# pcb2.net
KiCad netlist of a schematic drawn in EAGLE
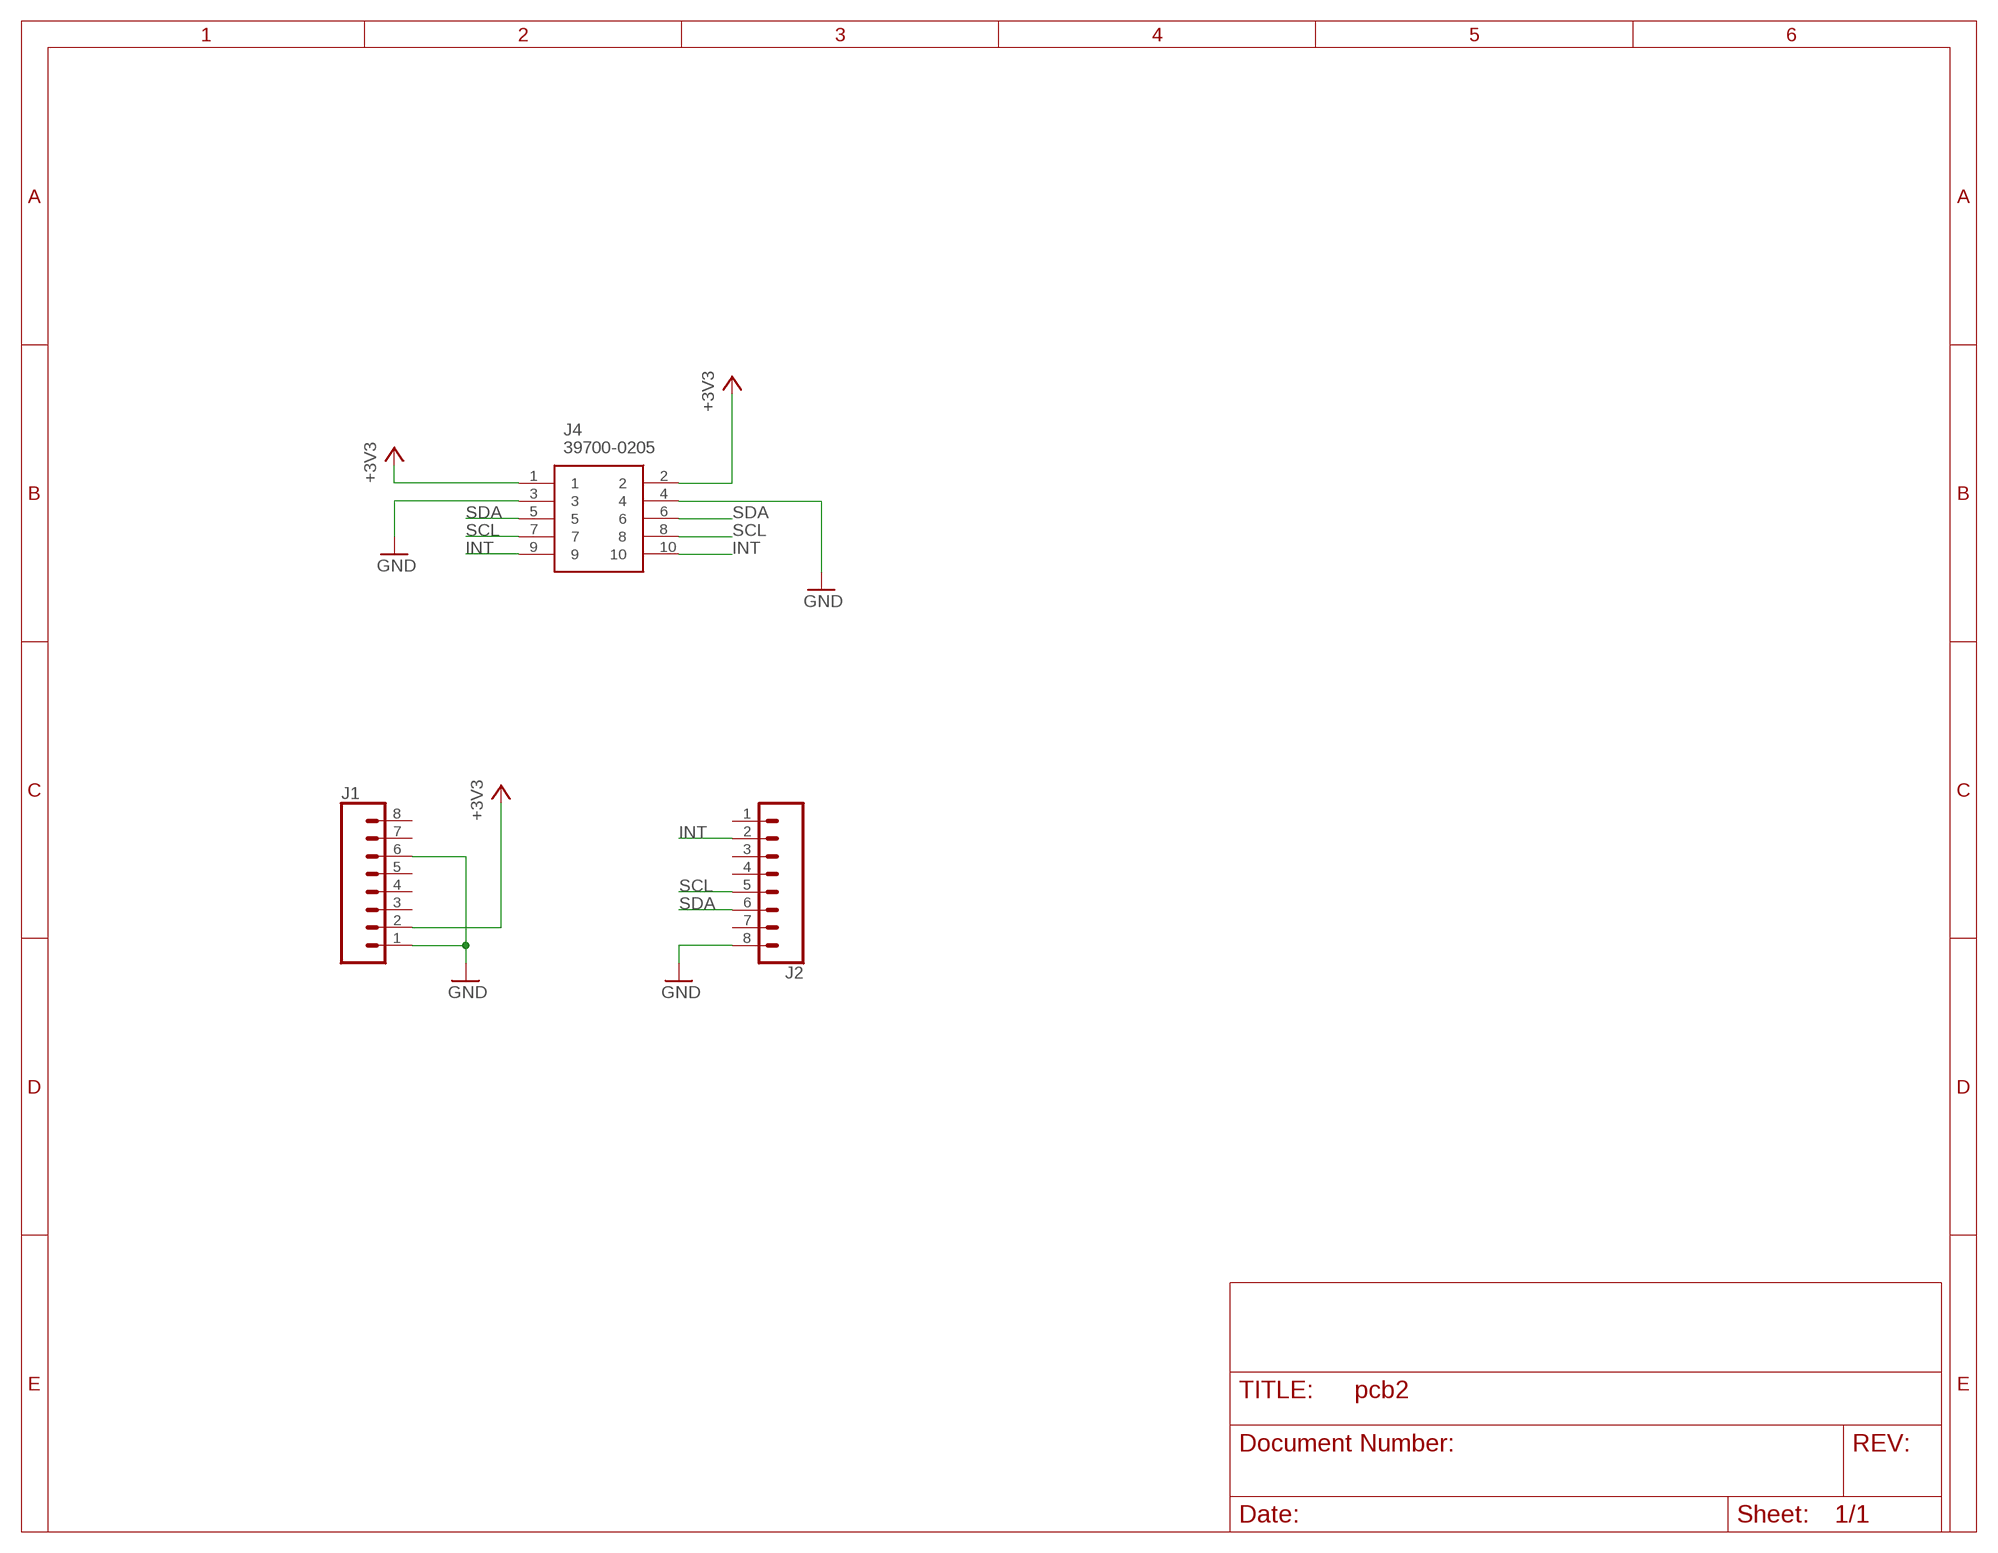
[diagram p0: schematic, sheet 1]

(export (version "E")
  (design (tool "Eeschema 10.0.6"))
  (components
    (comp (ref "J1")
      (value "CONN_08\"")
      (footprint "eagle-import:1X08")
      (libsource (lib "eagle-import") (part "CONN_08{dblquote}"))
    )
    (comp (ref "J2")
      (value "CONN_08\"")
      (footprint "eagle-import:1X08")
      (libsource (lib "eagle-import") (part "CONN_08{dblquote}"))
    )
    (comp (ref "J4")
      (value "39700-0205")
      (footprint "eagle-import:397000205")
      (fields (field (name "MOUSER_PART_NUMBER") "538-39700-0205"))
      (libsource (lib "eagle-import") (part "39700-0205"))
    )
  )
  (nets
    (net (code "1") (name "+3V3") (class "Default")
      (node (ref "J1") (pin "2") (pinfunction "2_2") (pintype "passive"))
      (node (ref "J4") (pin "1") (pinfunction "1_1") (pintype "bidirectional"))
      (node (ref "J4") (pin "2") (pinfunction "2_2") (pintype "bidirectional"))
    )
    (net (code "2") (name "/INT") (class "Default")
      (node (ref "J2") (pin "2") (pinfunction "2_2") (pintype "passive"))
      (node (ref "J4") (pin "10") (pinfunction "10_10") (pintype "bidirectional"))
      (node (ref "J4") (pin "9") (pinfunction "9_9") (pintype "bidirectional"))
    )
    (net (code "3") (name "/SCL") (class "Default")
      (node (ref "J2") (pin "5") (pinfunction "5_5") (pintype "passive"))
      (node (ref "J4") (pin "7") (pinfunction "7_7") (pintype "bidirectional"))
      (node (ref "J4") (pin "8") (pinfunction "8_8") (pintype "bidirectional"))
    )
    (net (code "4") (name "/SDA") (class "Default")
      (node (ref "J2") (pin "6") (pinfunction "6_6") (pintype "passive"))
      (node (ref "J4") (pin "5") (pinfunction "5_5") (pintype "bidirectional"))
      (node (ref "J4") (pin "6") (pinfunction "6_6") (pintype "bidirectional"))
    )
    (net (code "5") (name "GND") (class "Default")
      (node (ref "J1") (pin "1") (pinfunction "1_1") (pintype "passive"))
      (node (ref "J1") (pin "6") (pinfunction "6_6") (pintype "passive"))
      (node (ref "J2") (pin "8") (pinfunction "8_8") (pintype "passive"))
      (node (ref "J4") (pin "3") (pinfunction "3_3") (pintype "bidirectional"))
      (node (ref "J4") (pin "4") (pinfunction "4_4") (pintype "bidirectional"))
    )
    (net (code "6") (name "unconnected-(J1-Pad3)") (class "Default")
      (node (ref "J1") (pin "3") (pinfunction "3_3") (pintype "passive"))
    )
    (net (code "7") (name "unconnected-(J1-Pad4)") (class "Default")
      (node (ref "J1") (pin "4") (pinfunction "4_4") (pintype "passive"))
    )
    (net (code "8") (name "unconnected-(J1-Pad5)") (class "Default")
      (node (ref "J1") (pin "5") (pinfunction "5_5") (pintype "passive"))
    )
    (net (code "9") (name "unconnected-(J1-Pad7)") (class "Default")
      (node (ref "J1") (pin "7") (pinfunction "7_7") (pintype "passive"))
    )
    (net (code "10") (name "unconnected-(J1-Pad8)") (class "Default")
      (node (ref "J1") (pin "8") (pinfunction "8_8") (pintype "passive"))
    )
    (net (code "11") (name "unconnected-(J2-Pad1)") (class "Default")
      (node (ref "J2") (pin "1") (pinfunction "1_1") (pintype "passive"))
    )
    (net (code "12") (name "unconnected-(J2-Pad3)") (class "Default")
      (node (ref "J2") (pin "3") (pinfunction "3_3") (pintype "passive"))
    )
    (net (code "13") (name "unconnected-(J2-Pad4)") (class "Default")
      (node (ref "J2") (pin "4") (pinfunction "4_4") (pintype "passive"))
    )
    (net (code "14") (name "unconnected-(J2-Pad7)") (class "Default")
      (node (ref "J2") (pin "7") (pinfunction "7_7") (pintype "passive"))
    )
  )
)
